# LEDs_etc.net
KiCad netlist of a schematic drawn in Altium Designer
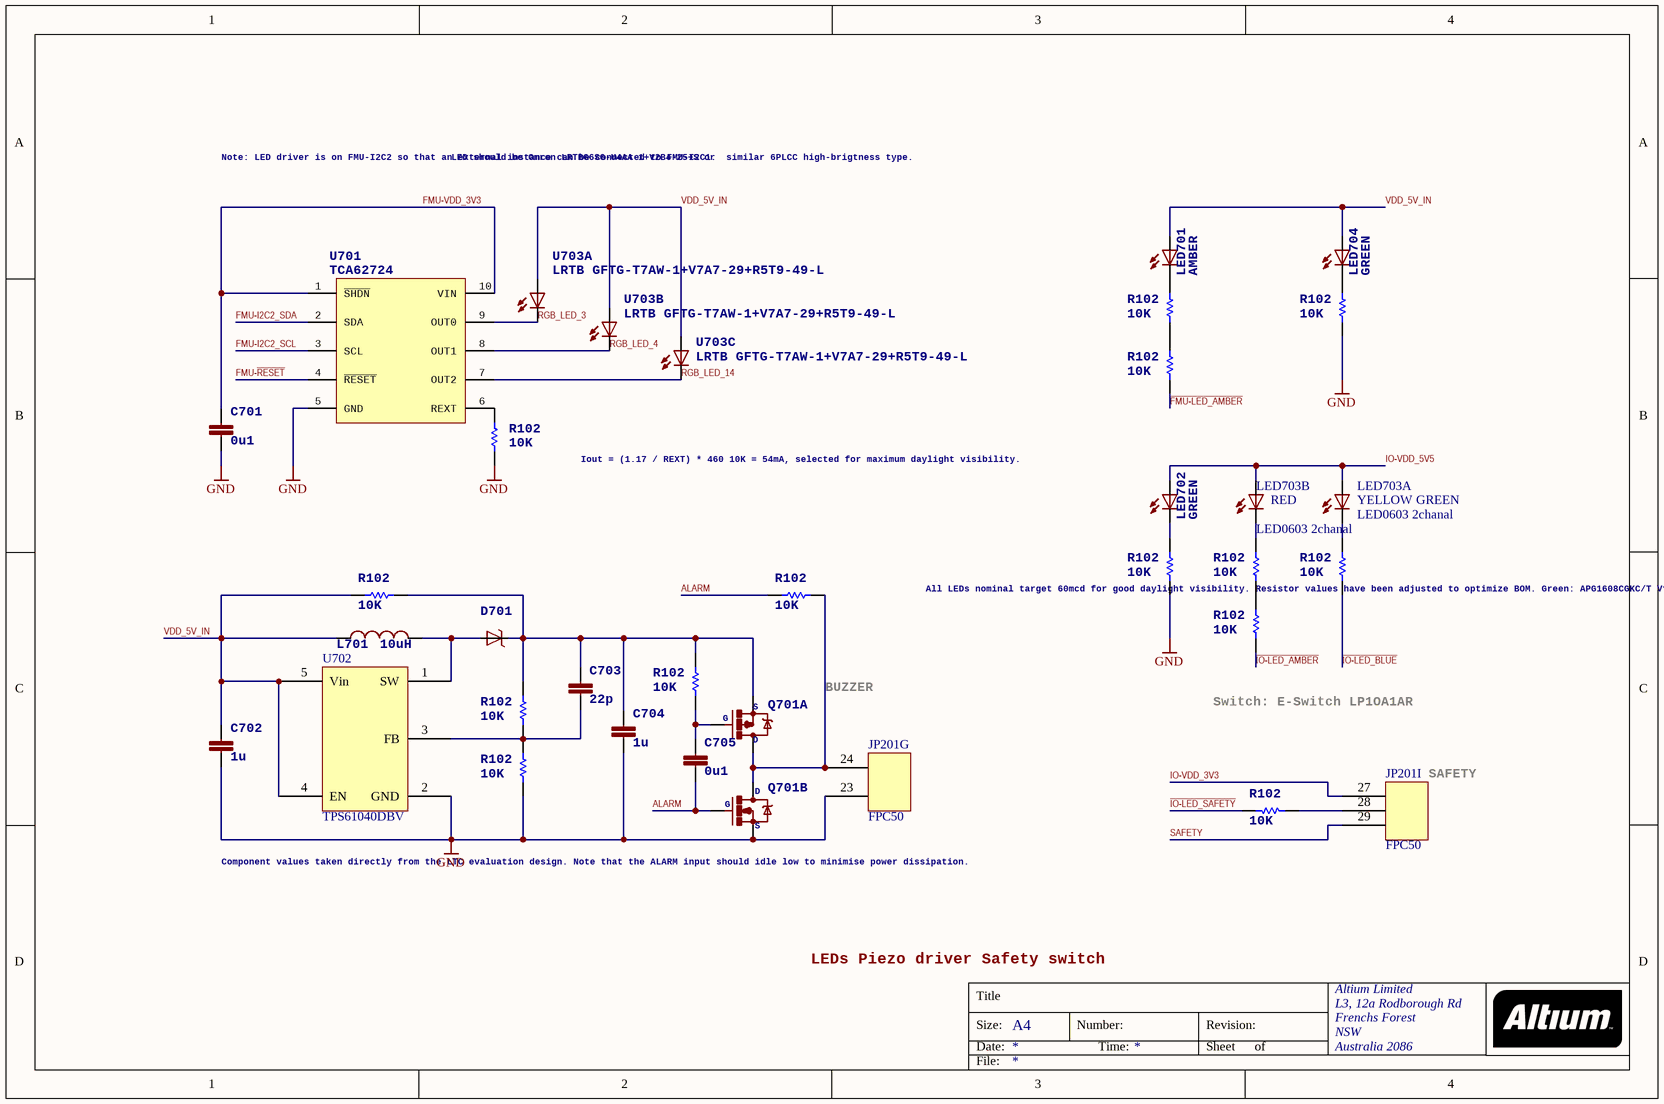
[diagram p0: LEDs etc.SchDoc]

(export (version "E")
  (design (tool "Eeschema 10.0.6"))
  (components
    (comp (ref "C701")
      (value "0u1")
      (footprint "0603-CAP")
      (description "<b>Capacitor</b>\nStandard 0603 ceramic capacitor, and 0.1\" leaded capacitor.")
      (fields
        (field (name "PARTNO") "CC0402ZRY5V7BB104")
        (field (name ">NAME") "C701")
        (field (name ">VALUE") "0u1")
      )
      (libsource (lib "pixhawk2") (part "CAP0402"))
    )
    (comp (ref "C702")
      (value "1u")
      (footprint "0603-CAP")
      (description "<b>Capacitor</b>\nStandard 0603 ceramic capacitor, and 0.1\" leaded capacitor.")
      (fields
        (field (name "PARTNO") "CC0603ZRY5V7BB105")
        (field (name ">NAME") "C702")
        (field (name ">VALUE") "1u")
      )
      (libsource (lib "pixhawk2") (part "CAP0603"))
    )
    (comp (ref "C703")
      (value "22p")
      (footprint "0603-CAP")
      (description "<b>Capacitor</b>\nStandard 0603 ceramic capacitor, and 0.1\" leaded capacitor.")
      (fields
        (field (name "PARTNO") "C0402C562K5RACTU")
        (field (name ">NAME") "C703")
        (field (name ">VALUE") "22p")
      )
      (libsource (lib "pixhawk2") (part "CAP0402"))
    )
    (comp (ref "C704")
      (value "1u")
      (footprint "0603-CAP")
      (description "<b>Capacitor</b>\nStandard 0603 ceramic capacitor, and 0.1\" leaded capacitor.")
      (fields
        (field (name "PARTNO") "C1005X5R1C474K050BC")
        (field (name ">NAME") "C704")
        (field (name ">VALUE") "1u")
      )
      (libsource (lib "pixhawk2") (part "CAP0402"))
    )
    (comp (ref "C705")
      (value "0u1")
      (footprint "0603-CAP")
      (description "<b>Capacitor</b>\nStandard 0603 ceramic capacitor, and 0.1\" leaded capacitor.")
      (fields
        (field (name "PARTNO") "CC0402ZRY5V7BB104")
        (field (name ">NAME") "C705")
        (field (name ">VALUE") "0u1")
      )
      (libsource (lib "pixhawk2") (part "CAP0402"))
    )
    (comp (ref "D701")
      (value "SS14 SOD323")
      (footprint "SOD323")
      (description "Schottky barrier diode in DO214AC, e.g. Fairchild SS14.")
      (libsource (lib "pixhawk2") (part "DIODE-SCHOTTKY_MSMP"))
    )
    (comp (ref "JP201") (value "FPC50") (footprint "FPC-0.5-50下接带锁") (libsource (lib "") (part "FPC50_1")))
    (comp (ref "L701")
      (value "10uH")
      (footprint "0805-IND")
      (fields
        (field (name "PARTNO") "MLZ2012M470W")
        (field (name ">NAME") "L701")
        (field (name ">VALUE") "10uH")
      )
      (libsource (lib "pixhawk2") (part "INDUCTOR0805"))
    )
    (comp (ref "LED701")
      (value "AMBER")
      (footprint "0603-LED")
      (fields
        (field (name "PARTNO") "APTD1608SECK")
        (field (name ">NAME") "LED701")
        (field (name ">VALUE") "AMBER")
      )
      (libsource (lib "pixhawk2") (part "LED0603"))
    )
    (comp (ref "LED702")
      (value "GREEN")
      (footprint "0603-LED")
      (fields
        (field (name "PARTNO") "APTD1608CGCK")
        (field (name ">NAME") "LED702")
        (field (name ">VALUE") "GREEN")
      )
      (libsource (lib "pixhawk2") (part "LED0603"))
    )
    (comp (ref "LED703")
      (value "LED0603 2chanal")
      (footprint "LED0603 2chanal")
      (libsource (lib "PX4") (part "LED0603 2chanal"))
    )
    (comp (ref "LED704")
      (value "GREEN")
      (footprint "0603-LED")
      (fields
        (field (name "PARTNO") "APTD1608CGCK")
        (field (name ">NAME") "LED704")
        (field (name ">VALUE") "GREEN")
      )
      (libsource (lib "pixhawk2") (part "LED0603"))
    )
    (comp (ref "Q701")
      (value "NX3008CBKS")
      (footprint "SOT363-6")
      (fields
        (field (name "PARTNO") "NTHD4102PT1G")
        (field (name "D") "D")
        (field (name "S") "S")
        (field (name "G") "G")
      )
      (libsource (lib "PX4") (part "N/PCHANNEL-Complementary-MOSFET"))
    )
    (comp (ref "R701")
      (value "10K")
      (footprint "0603-RES")
      (fields
        (field (name "PARTNO") "RC0402FR-0710KL")
        (field (name ">NAME") "R102")
        (field (name ">VALUE") "10K")
      )
      (libsource (lib "PX4") (part "RESISTOR0402-RES"))
    )
    (comp (ref "R702")
      (value "10K")
      (footprint "0603-RES")
      (fields
        (field (name "PARTNO") "RC0402FR-0710KL")
        (field (name ">NAME") "R102")
        (field (name ">VALUE") "10K")
      )
      (libsource (lib "PX4") (part "RESISTOR0402-RES"))
    )
    (comp (ref "R703")
      (value "10K")
      (footprint "0603-RES")
      (fields
        (field (name "PARTNO") "RC0402FR-0710KL")
        (field (name ">NAME") "R102")
        (field (name ">VALUE") "10K")
      )
      (libsource (lib "PX4") (part "RESISTOR0402-RES"))
    )
    (comp (ref "R704")
      (value "10K")
      (footprint "0603-RES")
      (fields
        (field (name "PARTNO") "RC0402FR-0710KL")
        (field (name ">NAME") "R102")
        (field (name ">VALUE") "10K")
      )
      (libsource (lib "PX4") (part "RESISTOR0402-RES"))
    )
    (comp (ref "R705")
      (value "10K")
      (footprint "0603-RES")
      (fields
        (field (name "PARTNO") "RC0402FR-0710KL")
        (field (name ">NAME") "R102")
        (field (name ">VALUE") "10K")
      )
      (libsource (lib "PX4") (part "RESISTOR0402-RES"))
    )
    (comp (ref "R706")
      (value "10K")
      (footprint "0603-RES")
      (fields
        (field (name "PARTNO") "RC0402FR-0710KL")
        (field (name ">NAME") "R102")
        (field (name ">VALUE") "10K")
      )
      (libsource (lib "PX4") (part "RESISTOR0402-RES"))
    )
    (comp (ref "R707")
      (value "10K")
      (footprint "0603-RES")
      (fields
        (field (name "PARTNO") "RC0402FR-0710KL")
        (field (name ">NAME") "R102")
        (field (name ">VALUE") "10K")
      )
      (libsource (lib "PX4") (part "RESISTOR0402-RES"))
    )
    (comp (ref "R708")
      (value "10K")
      (footprint "0603-RES")
      (fields
        (field (name "PARTNO") "RC0402FR-0710KL")
        (field (name ">NAME") "R102")
        (field (name ">VALUE") "10K")
      )
      (libsource (lib "PX4") (part "RESISTOR0402-RES"))
    )
    (comp (ref "R709")
      (value "10K")
      (footprint "0603-RES")
      (fields
        (field (name "PARTNO") "RC0402FR-0710KL")
        (field (name ">NAME") "R102")
        (field (name ">VALUE") "10K")
      )
      (libsource (lib "PX4") (part "RESISTOR0402-RES"))
    )
    (comp (ref "R710")
      (value "10K")
      (footprint "0603-RES")
      (fields
        (field (name "PARTNO") "RC0402FR-0710KL")
        (field (name ">NAME") "R102")
        (field (name ">VALUE") "10K")
      )
      (libsource (lib "PX4") (part "RESISTOR0402-RES"))
    )
    (comp (ref "R711")
      (value "10K")
      (footprint "0603-RES")
      (fields
        (field (name "PARTNO") "RC0402FR-0710KL")
        (field (name ">NAME") "R102")
        (field (name ">VALUE") "10K")
      )
      (libsource (lib "PX4") (part "RESISTOR0402-RES"))
    )
    (comp (ref "R712")
      (value "10K")
      (footprint "0603-RES")
      (fields
        (field (name "PARTNO") "RC0402FR-0710KL")
        (field (name ">NAME") "R102")
        (field (name ">VALUE") "10K")
      )
      (libsource (lib "PX4") (part "RESISTOR0402-RES"))
    )
    (comp (ref "R735")
      (value "10K")
      (footprint "0603-RES")
      (fields
        (field (name "PARTNO") "RC0402FR-0710KL")
        (field (name ">NAME") "R102")
        (field (name ">VALUE") "10K")
      )
      (libsource (lib "PX4") (part "RESISTOR0402-RES"))
    )
    (comp (ref "R736")
      (value "10K")
      (footprint "0603-RES")
      (fields
        (field (name "PARTNO") "RC0402FR-0710KL")
        (field (name ">NAME") "R102")
        (field (name ">VALUE") "10K")
      )
      (libsource (lib "PX4") (part "RESISTOR0402-RES"))
    )
    (comp (ref "U701")
      (value "TCA62724FMG")
      (footprint "SON10")
      (description "Toshiba TCA62724FMG I2C RGB LED driver")
      (fields (field (name ">NAME") "U701") (field (name "TCA62724") "TCA62724"))
      (libsource (lib "PX4") (part "TCA62724FMG"))
    )
    (comp (ref "U702")
      (value "TPS61040DBV")
      (footprint "SOT23-5")
      (description "Boost")
      (libsource (lib "PX4") (part "TPS61040"))
    )
    (comp (ref "U703")
      (value "LRTB GFTG-T7AW-1+V7A7-29+R5T9-49-L")
      (footprint "6-PLCC")
      (description "RGB LED with separate anode/cathode terminals")
      (libsource (lib "pixhawk2") (part "RGB-LED6-PLCC"))
    )
  )
  (nets
    (net (code "1") (name "/ALARM") (class "Default")
      (node (ref "C705") (pin "P$2") (pinfunction "2_P$2") (pintype "passive"))
      (node (ref "Q701") (pin "2") (pinfunction "G_2") (pintype "passive"))
      (node (ref "R706") (pin "P$2") (pinfunction "2_P$2") (pintype "passive"))
    )
    (net (code "2") (name "/FMU-I2C2_SCL") (class "Default")
      (node (ref "U701") (pin "3") (pinfunction "SCL_3") (pintype "passive"))
    )
    (net (code "3") (name "/FMU-I2C2_SDA") (class "Default")
      (node (ref "U701") (pin "2") (pinfunction "SDA_2") (pintype "passive"))
    )
    (net (code "4") (name "/FMU-VDD_3V3") (class "Default")
      (node (ref "C701") (pin "P$1") (pinfunction "1_P$1") (pintype "passive"))
      (node (ref "U701") (pin "1") (pinfunction "~{SHDN}_1") (pintype "passive"))
      (node (ref "U701") (pin "10") (pinfunction "VIN_10") (pintype "power_in"))
    )
    (net (code "5") (name "/FMU-~{RESET}") (class "Default")
      (node (ref "U701") (pin "4") (pinfunction "~{RESET}_4") (pintype "passive"))
    )
    (net (code "6") (name "/IO-VDD_3V3") (class "Default")
      (node (ref "JP201") (pin "27") (pintype "passive"))
    )
    (net (code "7") (name "/IO-VDD_5V5") (class "Default")
      (node (ref "LED702") (pin "A") (pinfunction "A_A") (pintype "passive"))
      (node (ref "LED703") (pin "3") (pinfunction "A_3") (pintype "passive"))
      (node (ref "LED703") (pin "4") (pinfunction "A_4") (pintype "passive"))
    )
    (net (code "8") (name "/RGB_LED_3") (class "Default")
      (node (ref "U701") (pin "9") (pinfunction "OUT0_9") (pintype "open_collector"))
      (node (ref "U703") (pin "C1") (pinfunction "C_C1") (pintype "passive"))
    )
    (net (code "9") (name "/RGB_LED_4") (class "Default")
      (node (ref "U701") (pin "8") (pinfunction "OUT1_8") (pintype "open_collector"))
      (node (ref "U703") (pin "C2") (pinfunction "C_C2") (pintype "passive"))
    )
    (net (code "10") (name "/RGB_LED_14") (class "Default")
      (node (ref "U701") (pin "7") (pinfunction "OUT2_7") (pintype "open_collector"))
      (node (ref "U703") (pin "C3") (pinfunction "C_C3") (pintype "passive"))
    )
    (net (code "11") (name "/SAFETY") (class "Default") (node (ref "JP201") (pin "29") (pintype "passive")))
    (net (code "12") (name "/VDD_5V_IN") (class "Default")
      (node (ref "C702") (pin "P$1") (pinfunction "1_P$1") (pintype "passive"))
      (node (ref "L701") (pin "P$1") (pinfunction "1_P$1") (pintype "passive"))
      (node (ref "LED701") (pin "A") (pinfunction "A_A") (pintype "passive"))
      (node (ref "LED704") (pin "A") (pinfunction "A_A") (pintype "passive"))
      (node (ref "R705") (pin "P$2") (pinfunction "2_P$2") (pintype "passive"))
      (node (ref "U702") (pin "4") (pinfunction "EN_4") (pintype "passive"))
      (node (ref "U702") (pin "5") (pinfunction "Vin_5") (pintype "passive"))
      (node (ref "U703") (pin "A1") (pinfunction "A_A1") (pintype "passive"))
      (node (ref "U703") (pin "A2") (pinfunction "A_A2") (pintype "passive"))
      (node (ref "U703") (pin "A3") (pinfunction "A_A3") (pintype "passive"))
    )
    (net (code "13") (name "/~{FMU-LED_AMBER}") (class "Default")
      (node (ref "R707") (pin "P$1") (pinfunction "1_P$1") (pintype "passive"))
    )
    (net (code "14") (name "/~{IO-LED_AMBER}") (class "Default")
      (node (ref "R709") (pin "P$1") (pinfunction "1_P$1") (pintype "passive"))
    )
    (net (code "15") (name "/~{IO-LED_BLUE}") (class "Default")
      (node (ref "R712") (pin "P$1") (pinfunction "1_P$1") (pintype "passive"))
    )
    (net (code "16") (name "/~{IO-LED_SAFETY}") (class "Default")
      (node (ref "R710") (pin "P$2") (pinfunction "2_P$2") (pintype "passive"))
    )
    (net (code "17") (name "GND") (class "Default")
      (node (ref "C701") (pin "P$2") (pinfunction "2_P$2") (pintype "passive"))
      (node (ref "C702") (pin "P$2") (pinfunction "2_P$2") (pintype "passive"))
      (node (ref "C704") (pin "P$2") (pinfunction "2_P$2") (pintype "passive"))
      (node (ref "JP201") (pin "23") (pintype "passive"))
      (node (ref "Q701") (pin "1") (pinfunction "S_1") (pintype "passive"))
      (node (ref "R703") (pin "P$2") (pinfunction "2_P$2") (pintype "passive"))
      (node (ref "R704") (pin "P$1") (pinfunction "1_P$1") (pintype "passive"))
      (node (ref "R708") (pin "P$1") (pinfunction "1_P$1") (pintype "passive"))
      (node (ref "R711") (pin "P$1") (pinfunction "1_P$1") (pintype "passive"))
      (node (ref "U701") (pin "5") (pinfunction "GND_5") (pintype "power_in"))
      (node (ref "U702") (pin "2") (pinfunction "GND_2") (pintype "passive"))
    )
    (net (code "18") (name "Net-(C703-1)") (class "Default")
      (node (ref "C703") (pin "P$1") (pinfunction "1_P$1") (pintype "passive"))
      (node (ref "C704") (pin "P$1") (pinfunction "1_P$1") (pintype "passive"))
      (node (ref "D701") (pin "C") (pinfunction "C_C") (pintype "passive"))
      (node (ref "Q701") (pin "4") (pinfunction "S_4") (pintype "passive"))
      (node (ref "R701") (pin "P$1") (pinfunction "1_P$1") (pintype "passive"))
      (node (ref "R702") (pin "P$1") (pinfunction "1_P$1") (pintype "passive"))
      (node (ref "R705") (pin "P$1") (pinfunction "1_P$1") (pintype "passive"))
    )
    (net (code "19") (name "Net-(C703-2)") (class "Default")
      (node (ref "C703") (pin "P$2") (pinfunction "2_P$2") (pintype "passive"))
      (node (ref "R702") (pin "P$2") (pinfunction "2_P$2") (pintype "passive"))
      (node (ref "R703") (pin "P$1") (pinfunction "1_P$1") (pintype "passive"))
      (node (ref "U702") (pin "3") (pinfunction "FB_3") (pintype "passive"))
    )
    (net (code "20") (name "Net-(C705-1)") (class "Default")
      (node (ref "C705") (pin "P$1") (pinfunction "1_P$1") (pintype "passive"))
      (node (ref "Q701") (pin "5") (pinfunction "G_5") (pintype "passive"))
      (node (ref "R701") (pin "P$2") (pinfunction "2_P$2") (pintype "passive"))
    )
    (net (code "21") (name "Net-(L701-2)") (class "Default")
      (node (ref "D701") (pin "A") (pinfunction "A_A") (pintype "passive"))
      (node (ref "L701") (pin "P$2") (pinfunction "2_P$2") (pintype "passive"))
      (node (ref "U702") (pin "1") (pinfunction "SW_1") (pintype "passive"))
    )
    (net (code "22") (name "Net-(LED703A-C)") (class "Default")
      (node (ref "LED703") (pin "1") (pinfunction "C_1") (pintype "passive"))
      (node (ref "R712") (pin "P$2") (pinfunction "2_P$2") (pintype "passive"))
    )
    (net (code "23") (name "Net-(LED703B-C)") (class "Default")
      (node (ref "LED703") (pin "2") (pinfunction "C_2") (pintype "passive"))
      (node (ref "R736") (pin "P$2") (pinfunction "2_P$2") (pintype "passive"))
    )
    (net (code "24") (name "Net-(Q701A-D)") (class "Default")
      (node (ref "JP201") (pin "24") (pintype "passive"))
      (node (ref "Q701") (pin "3") (pinfunction "D_3") (pintype "passive"))
      (node (ref "Q701") (pin "6") (pinfunction "D_6") (pintype "passive"))
      (node (ref "R706") (pin "P$1") (pinfunction "1_P$1") (pintype "passive"))
    )
    (net (code "25") (name "Net-(R704-2)") (class "Default")
      (node (ref "R704") (pin "P$2") (pinfunction "2_P$2") (pintype "passive"))
      (node (ref "U701") (pin "6") (pinfunction "REXT_6") (pintype "passive"))
    )
    (net (code "26") (name "Net-(R707-2)") (class "Default")
      (node (ref "R707") (pin "P$2") (pinfunction "2_P$2") (pintype "passive"))
      (node (ref "R735") (pin "P$1") (pinfunction "1_P$1") (pintype "passive"))
    )
    (net (code "27") (name "Net-(R708-2)") (class "Default")
      (node (ref "LED702") (pin "C") (pinfunction "C_C") (pintype "passive"))
      (node (ref "R708") (pin "P$2") (pinfunction "2_P$2") (pintype "passive"))
    )
    (net (code "28") (name "Net-(R709-2)") (class "Default")
      (node (ref "R709") (pin "P$2") (pinfunction "2_P$2") (pintype "passive"))
      (node (ref "R736") (pin "P$1") (pinfunction "1_P$1") (pintype "passive"))
    )
    (net (code "29") (name "Net-(R710-1)") (class "Default")
      (node (ref "JP201") (pin "28") (pintype "passive"))
      (node (ref "R710") (pin "P$1") (pinfunction "1_P$1") (pintype "passive"))
    )
    (net (code "30") (name "Net-(R711-2)") (class "Default")
      (node (ref "LED704") (pin "C") (pinfunction "C_C") (pintype "passive"))
      (node (ref "R711") (pin "P$2") (pinfunction "2_P$2") (pintype "passive"))
    )
    (net (code "31") (name "Net-(R735-2)") (class "Default")
      (node (ref "LED701") (pin "C") (pinfunction "C_C") (pintype "passive"))
      (node (ref "R735") (pin "P$2") (pinfunction "2_P$2") (pintype "passive"))
    )
  )
)
